# Power_Supply.net
KiCad netlist of a schematic drawn in Altium Designer
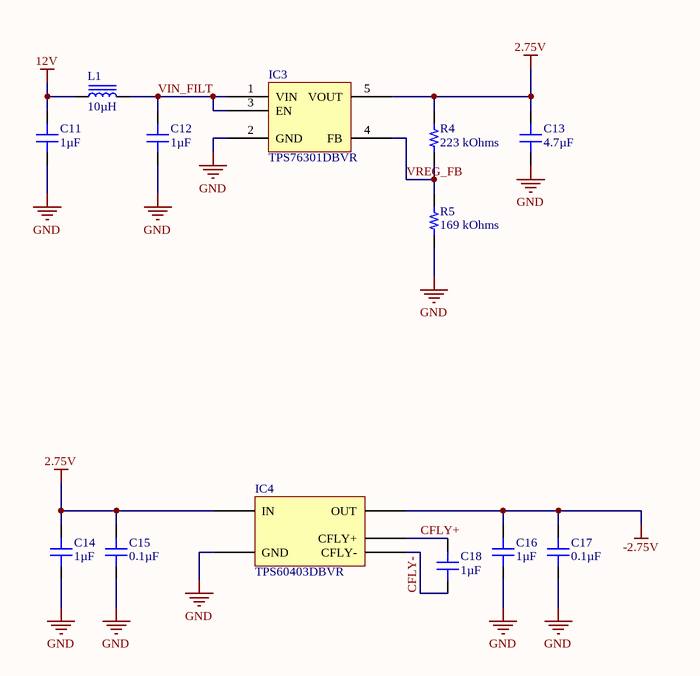
[diagram p0: Power Supply.SchDoc]

(export (version "E")
  (design (tool "Eeschema 10.0.6"))
  (components
    (comp (ref "C11")
      (value "1µF")
      (footprint "CAP 0603_1608")
      (description "CAP CER 1UF 25V X5R 0603")
      (fields (field (name "PART NUMBER") "CC0603KRX5R8BB105") (field (name "MANUFACTURER") "Yageo"))
      (libsource (lib "Celestial Altium Library - altium_library") (part "Capacitor"))
    )
    (comp (ref "C12")
      (value "1µF")
      (footprint "CAP 0603_1608")
      (description "CAP CER 1UF 25V X5R 0603")
      (fields (field (name "PART NUMBER") "CC0603KRX5R8BB105") (field (name "MANUFACTURER") "Yageo"))
      (libsource (lib "Celestial Altium Library - altium_library") (part "Capacitor"))
    )
    (comp (ref "C13")
      (value "4.7µF")
      (footprint "CAP 0603_1608")
      (description "CAP CER 4.7UF 6.3V X5R 0603")
      (fields
        (field (name "PART NUMBER") "CL10A475MQ8NNNC")
        (field (name "MANUFACTURER") "Samsung Electro-Mechanics")
      )
      (libsource (lib "Celestial Altium Library - altium_library") (part "Capacitor"))
    )
    (comp (ref "C14")
      (value "1µF")
      (footprint "CAP 0603_1608")
      (description "CAP CER 1UF 25V X5R 0603")
      (fields (field (name "PART NUMBER") "CC0603KRX5R8BB105") (field (name "MANUFACTURER") "Yageo"))
      (libsource (lib "Celestial Altium Library - altium_library") (part "Capacitor"))
    )
    (comp (ref "C15")
      (value "0.1µF")
      (footprint "CAP 0603_1608")
      (description "CAP CER 0.1UF 25V Y5V 0603")
      (fields (field (name "PART NUMBER") "CC0603MRY5V8BB104") (field (name "MANUFACTURER") "Yageo"))
      (libsource (lib "Celestial Altium Library - altium_library") (part "Capacitor"))
    )
    (comp (ref "C16")
      (value "1µF")
      (footprint "CAP 0603_1608")
      (description "CAP CER 1UF 25V X5R 0603")
      (fields (field (name "PART NUMBER") "CC0603KRX5R8BB105") (field (name "MANUFACTURER") "Yageo"))
      (libsource (lib "Celestial Altium Library - altium_library") (part "Capacitor"))
    )
    (comp (ref "C17")
      (value "0.1µF")
      (footprint "CAP 0603_1608")
      (description "CAP CER 0.1UF 25V Y5V 0603")
      (fields (field (name "PART NUMBER") "CC0603MRY5V8BB104") (field (name "MANUFACTURER") "Yageo"))
      (libsource (lib "Celestial Altium Library - altium_library") (part "Capacitor"))
    )
    (comp (ref "C18")
      (value "1µF")
      (footprint "CAP 0603_1608")
      (description "CAP CER 1UF 25V X5R 0603")
      (fields (field (name "PART NUMBER") "CC0603KRX5R8BB105") (field (name "MANUFACTURER") "Yageo"))
      (libsource (lib "Celestial Altium Library - altium_library") (part "Capacitor"))
    )
    (comp (ref "IC3")
      (value "TPS76301DBVR")
      (footprint "TI SOT-23-5 DBV")
      (description "IC REG LIN POS ADJ 150MA SOT23-5")
      (fields (field (name "MANUFACTURER") "Texas Instruments"))
      (libsource (lib "Celestial Altium Library - altium_library") (part "TI TPS76301"))
    )
    (comp (ref "IC4")
      (value "TPS60403DBVR")
      (footprint "TI SOT-23-5 DBV")
      (description "IC REG CHARG PUMP INV 60MA SOT23")
      (fields (field (name "MANUFACTURER") "Texas Instruments"))
      (libsource (lib "Celestial Altium Library - altium_library") (part "TI TPS60403"))
    )
    (comp (ref "L1")
      (value "10µH")
      (footprint "IND 0806_2016")
      (description "FIXED IND 10UH 245MA 820 MOHM")
      (fields (field (name "PART NUMBER") "LBC2016T100K") (field (name "MANUFACTURER") "Taiyo Yuden"))
      (libsource (lib "Celestial Altium Library - altium_library") (part "Inductor"))
    )
    (comp (ref "R4")
      (value "223 kOhms")
      (footprint "RES 0603_1608")
      (description "RESISTOR THIN FILM")
      (fields
        (field (name "PART NUMBER") "RN73H1JTTD2233D100")
        (field (name "MANUFACTURER") "KOA Speer Electronics, Inc.")
      )
      (libsource (lib "Celestial Altium Library - altium_library") (part "Resistor"))
    )
    (comp (ref "R5")
      (value "169 kOhms")
      (footprint "RES 0603_1608")
      (description "RES SMD 169K OHM 1% 1/10W 0603")
      (fields
        (field (name "PART NUMBER") "ERJ-3EKF1693V")
        (field (name "MANUFACTURER") "Panasonic Electronic Components")
      )
      (libsource (lib "Celestial Altium Library - altium_library") (part "Resistor"))
    )
  )
  (nets
    (net (code "1") (name "-2.75V") (class "Default")
      (node (ref "C16") (pin "2") (pinfunction "2_2") (pintype "passive"))
      (node (ref "C17") (pin "2") (pinfunction "2_2") (pintype "passive"))
      (node (ref "IC4") (pin "1") (pinfunction "OUT_1") (pintype "passive"))
    )
    (net (code "2") (name "/CFLY+") (class "Default")
      (node (ref "C18") (pin "2") (pinfunction "2_2") (pintype "passive"))
      (node (ref "IC4") (pin "5") (pinfunction "CFLY+_5") (pintype "passive"))
    )
    (net (code "3") (name "/CFLY-") (class "Default")
      (node (ref "C18") (pin "1") (pinfunction "1_1") (pintype "passive"))
      (node (ref "IC4") (pin "3") (pinfunction "CFLY-_3") (pintype "passive"))
    )
    (net (code "4") (name "/VIN_FILT") (class "Default")
      (node (ref "C12") (pin "2") (pinfunction "2_2") (pintype "passive"))
      (node (ref "IC3") (pin "1") (pinfunction "VIN_1") (pintype "passive"))
      (node (ref "IC3") (pin "3") (pinfunction "EN_3") (pintype "passive"))
      (node (ref "L1") (pin "2") (pinfunction "2_2") (pintype "passive"))
    )
    (net (code "5") (name "/VREG_FB") (class "Default")
      (node (ref "IC3") (pin "4") (pinfunction "FB_4") (pintype "passive"))
      (node (ref "R4") (pin "1") (pinfunction "1_1") (pintype "passive"))
      (node (ref "R5") (pin "2") (pinfunction "2_2") (pintype "passive"))
    )
    (net (code "6") (name "2.75V") (class "Default")
      (node (ref "C13") (pin "2") (pinfunction "2_2") (pintype "passive"))
      (node (ref "C14") (pin "2") (pinfunction "2_2") (pintype "passive"))
      (node (ref "C15") (pin "2") (pinfunction "2_2") (pintype "passive"))
      (node (ref "IC3") (pin "5") (pinfunction "VOUT_5") (pintype "passive"))
      (node (ref "IC4") (pin "2") (pinfunction "IN_2") (pintype "passive"))
      (node (ref "R4") (pin "2") (pinfunction "2_2") (pintype "passive"))
    )
    (net (code "7") (name "12V") (class "Default")
      (node (ref "C11") (pin "2") (pinfunction "2_2") (pintype "passive"))
      (node (ref "L1") (pin "1") (pinfunction "1_1") (pintype "passive"))
    )
    (net (code "8") (name "GND") (class "Default")
      (node (ref "C11") (pin "1") (pinfunction "1_1") (pintype "passive"))
      (node (ref "C12") (pin "1") (pinfunction "1_1") (pintype "passive"))
      (node (ref "C13") (pin "1") (pinfunction "1_1") (pintype "passive"))
      (node (ref "C14") (pin "1") (pinfunction "1_1") (pintype "passive"))
      (node (ref "C15") (pin "1") (pinfunction "1_1") (pintype "passive"))
      (node (ref "C16") (pin "1") (pinfunction "1_1") (pintype "passive"))
      (node (ref "C17") (pin "1") (pinfunction "1_1") (pintype "passive"))
      (node (ref "IC3") (pin "2") (pinfunction "GND_2") (pintype "passive"))
      (node (ref "IC4") (pin "4") (pinfunction "GND_4") (pintype "passive"))
      (node (ref "R5") (pin "1") (pinfunction "1_1") (pintype "passive"))
    )
  )
)
